# haccess.net
KiCad netlist of a schematic drawn in EAGLE
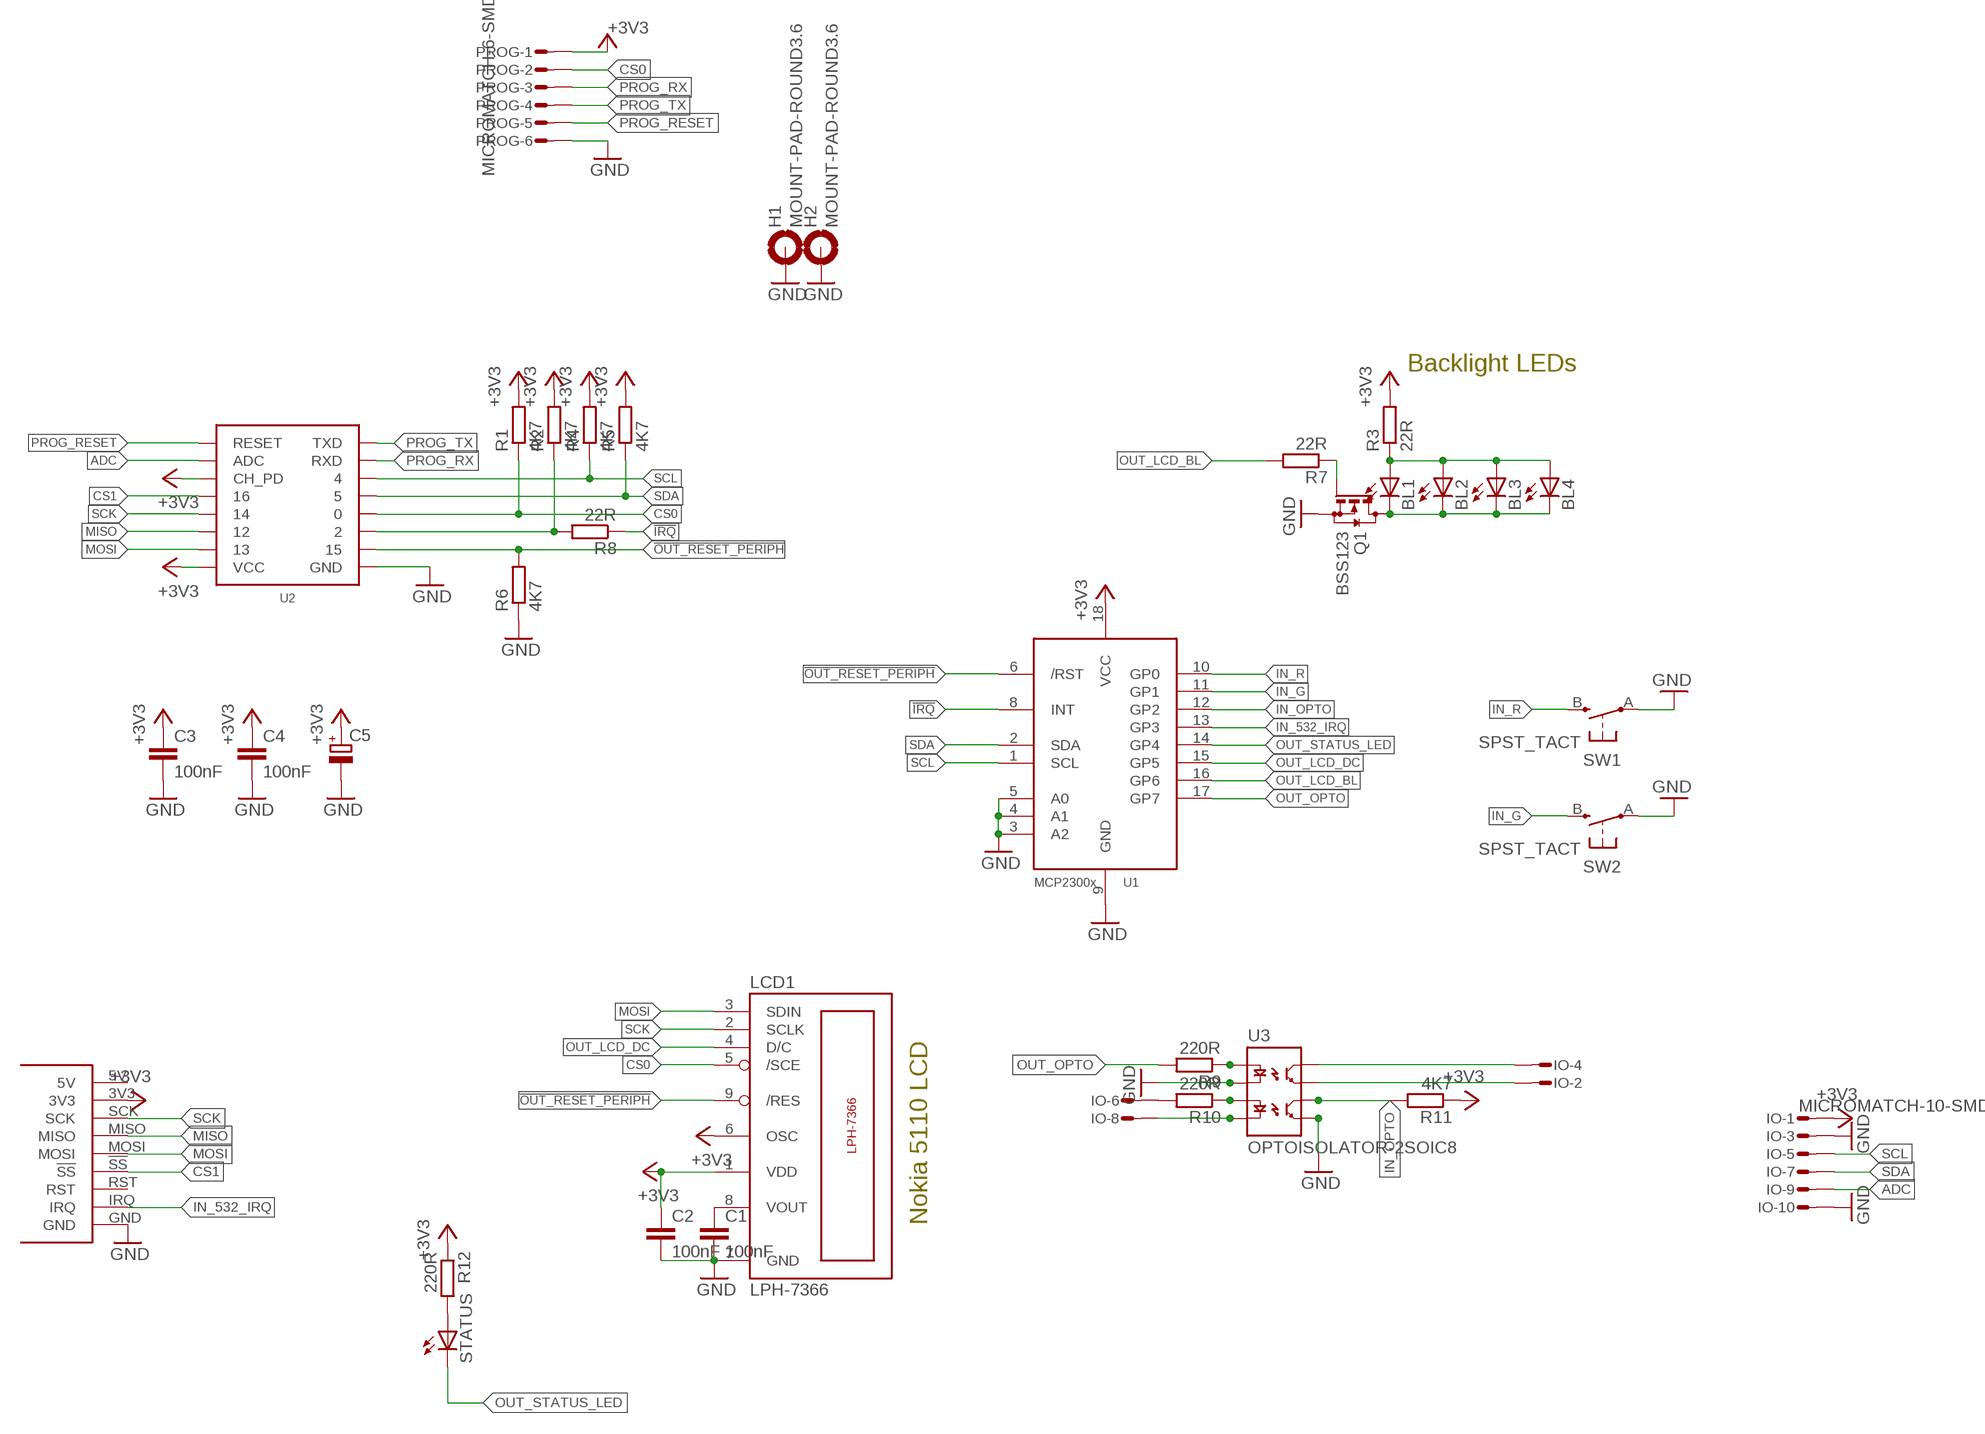
[diagram p0: schematic, sheet 1]

(export (version "E")
  (design (tool "Eeschema 10.0.6"))
  (components
    (comp (ref "BL1")
      (value "LEDCHIPLED_0805")
      (footprint "eagle-import:CHIPLED_0805")
      (libsource (lib "eagle-import") (part "LEDCHIPLED_0805"))
    )
    (comp (ref "BL2")
      (value "LEDCHIPLED_0805")
      (footprint "eagle-import:CHIPLED_0805")
      (libsource (lib "eagle-import") (part "LEDCHIPLED_0805"))
    )
    (comp (ref "BL3")
      (value "LEDCHIPLED_0805")
      (footprint "eagle-import:CHIPLED_0805")
      (libsource (lib "eagle-import") (part "LEDCHIPLED_0805"))
    )
    (comp (ref "BL4")
      (value "LEDCHIPLED_0805")
      (footprint "eagle-import:CHIPLED_0805")
      (libsource (lib "eagle-import") (part "LEDCHIPLED_0805"))
    )
    (comp (ref "C1")
      (value "100nF")
      (footprint "eagle-import:C0805K")
      (libsource (lib "eagle-import") (part "C-EUC0805K"))
    )
    (comp (ref "C2")
      (value "100nF")
      (footprint "eagle-import:C0805K")
      (libsource (lib "eagle-import") (part "C-EUC0805K"))
    )
    (comp (ref "C3")
      (value "100nF")
      (footprint "eagle-import:C0805K")
      (libsource (lib "eagle-import") (part "C-EUC0805K"))
    )
    (comp (ref "C4")
      (value "100nF")
      (footprint "eagle-import:C0805K")
      (libsource (lib "eagle-import") (part "C-EUC0805K"))
    )
    (comp (ref "C5")
      (value "CPOL-EUSMCB")
      (footprint "eagle-import:SMC_B")
      (libsource (lib "eagle-import") (part "CPOL-EUSMCB"))
    )
    (comp (ref "H1")
      (value "MOUNT-PAD-ROUND3.6")
      (footprint "eagle-import:3,6-PAD")
      (libsource (lib "eagle-import") (part "MOUNT-PAD-ROUND3.6"))
    )
    (comp (ref "H2")
      (value "MOUNT-PAD-ROUND3.6")
      (footprint "eagle-import:3,6-PAD")
      (libsource (lib "eagle-import") (part "MOUNT-PAD-ROUND3.6"))
    )
    (comp (ref "IO")
      (value "MICROMATCH-10-SMD")
      (footprint "eagle-import:MICROMATCH-10-SMD")
      (libsource (lib "eagle-import") (part "MICROMATCH-10-SMD"))
    )
    (comp (ref "LCD1")
      (value "LPH-7366")
      (footprint "eagle-import:LPH-7366")
      (libsource (lib "eagle-import") (part "LPH-7366"))
    )
    (comp (ref "PROG")
      (value "MICROMATCH-6-SMD")
      (footprint "eagle-import:MICROMATCH-6-SMD")
      (libsource (lib "eagle-import") (part "MICROMATCH-6-SMD"))
    )
    (comp (ref "Q1")
      (value "BSS123")
      (footprint "eagle-import:SOT23")
      (libsource (lib "eagle-import") (part "BSS123"))
    )
    (comp (ref "R1")
      (value "4K7")
      (footprint "eagle-import:R0603")
      (libsource (lib "eagle-import") (part "R-EU_R0603"))
    )
    (comp (ref "R2")
      (value "4K7")
      (footprint "eagle-import:R0603")
      (libsource (lib "eagle-import") (part "R-EU_R0603"))
    )
    (comp (ref "R3")
      (value "22R")
      (footprint "eagle-import:R0603")
      (libsource (lib "eagle-import") (part "R-EU_R0603"))
    )
    (comp (ref "R4")
      (value "4K7")
      (footprint "eagle-import:R0603")
      (libsource (lib "eagle-import") (part "R-EU_R0603"))
    )
    (comp (ref "R5")
      (value "4K7")
      (footprint "eagle-import:R0603")
      (libsource (lib "eagle-import") (part "R-EU_R0603"))
    )
    (comp (ref "R6")
      (value "4K7")
      (footprint "eagle-import:R0603")
      (libsource (lib "eagle-import") (part "R-EU_R0603"))
    )
    (comp (ref "R7")
      (value "22R")
      (footprint "eagle-import:R0603")
      (libsource (lib "eagle-import") (part "R-EU_R0603"))
    )
    (comp (ref "R8")
      (value "22R")
      (footprint "eagle-import:R0603")
      (libsource (lib "eagle-import") (part "R-EU_R0603"))
    )
    (comp (ref "R9")
      (value "220R")
      (footprint "eagle-import:R0603")
      (libsource (lib "eagle-import") (part "R-EU_R0603"))
    )
    (comp (ref "R10")
      (value "220R")
      (footprint "eagle-import:R0603")
      (libsource (lib "eagle-import") (part "R-EU_R0603"))
    )
    (comp (ref "R11")
      (value "4K7")
      (footprint "eagle-import:R0603")
      (libsource (lib "eagle-import") (part "R-EU_R0603"))
    )
    (comp (ref "R12")
      (value "220R")
      (footprint "eagle-import:R0603")
      (libsource (lib "eagle-import") (part "R-EU_R0603"))
    )
    (comp (ref "STATUS")
      (value "LEDCHIP-LED0805")
      (footprint "eagle-import:CHIP-LED0805")
      (libsource (lib "eagle-import") (part "LEDCHIP-LED0805"))
    )
    (comp (ref "SW1")
      (value "SPST_TACT")
      (footprint "eagle-import:SKPMAPE010")
      (libsource (lib "eagle-import") (part "SPST_TACT"))
    )
    (comp (ref "SW2")
      (value "SPST_TACT")
      (footprint "eagle-import:SKPMAPE010")
      (libsource (lib "eagle-import") (part "SPST_TACT"))
    )
    (comp (ref "U$1")
      (value "PN532SMALLMODULE")
      (footprint "eagle-import:SMALL-MODULE")
      (libsource (lib "eagle-import") (part "PN532SMALLMODULE"))
    )
    (comp (ref "U1")
      (value "MCP2300X/SO")
      (footprint "eagle-import:SO18W")
      (libsource (lib "eagle-import") (part "MCP2300X/SO"))
    )
    (comp (ref "U2")
      (value "ESP826607B")
      (footprint "eagle-import:ESP-07B")
      (libsource (lib "eagle-import") (part "ESP826607B"))
    )
    (comp (ref "U3")
      (value "OPTOISOLATOR-2SOIC8")
      (footprint "eagle-import:SO08-2")
      (libsource (lib "eagle-import") (part "OPTOISOLATOR-2SOIC8"))
    )
  )
  (nets
    (net (code "1") (name "+3V3") (class "Default")
      (node (ref "C2") (pin "1") (pinfunction "1_1") (pintype "passive"))
      (node (ref "C3") (pin "1") (pinfunction "1_1") (pintype "passive"))
      (node (ref "C4") (pin "1") (pinfunction "1_1") (pintype "passive"))
      (node (ref "C5") (pin "+") (pinfunction "+_+") (pintype "passive"))
      (node (ref "IO") (pin "1") (pinfunction "S_1") (pintype "passive"))
      (node (ref "LCD1") (pin "1") (pinfunction "VDD_1") (pintype "power_in"))
      (node (ref "LCD1") (pin "6") (pinfunction "OSC_6") (pintype "passive"))
      (node (ref "PROG") (pin "1") (pinfunction "S_1") (pintype "passive"))
      (node (ref "R1") (pin "2") (pinfunction "2_2") (pintype "passive"))
      (node (ref "R11") (pin "1") (pinfunction "1_1") (pintype "passive"))
      (node (ref "R12") (pin "1") (pinfunction "1_1") (pintype "passive"))
      (node (ref "R2") (pin "2") (pinfunction "2_2") (pintype "passive"))
      (node (ref "R3") (pin "2") (pinfunction "2_2") (pintype "passive"))
      (node (ref "R4") (pin "2") (pinfunction "2_2") (pintype "passive"))
      (node (ref "R5") (pin "2") (pinfunction "2_2") (pintype "passive"))
      (node (ref "U$1") (pin "3V3") (pinfunction "3V3_3V3") (pintype "bidirectional"))
      (node (ref "U1") (pin "18") (pinfunction "VCC_18") (pintype "power_in"))
      (node (ref "U2") (pin "CH_PD") (pinfunction "CH_PD_CH_PD") (pintype "input"))
      (node (ref "U2") (pin "VCC") (pinfunction "VCC_VCC") (pintype "power_in"))
    )
    (net (code "2") (name "/~{IRQ}") (class "Default")
      (node (ref "R8") (pin "1") (pinfunction "1_1") (pintype "passive"))
      (node (ref "U1") (pin "8") (pinfunction "INT_8") (pintype "output"))
    )
    (net (code "3") (name "/~{OUT_RESET_PERIPH}") (class "Default")
      (node (ref "LCD1") (pin "9") (pinfunction "/RES_9") (pintype "input"))
      (node (ref "R6") (pin "2") (pinfunction "2_2") (pintype "passive"))
      (node (ref "U1") (pin "6") (pinfunction "/RST_6") (pintype "input"))
      (node (ref "U2") (pin "GPIO15") (pinfunction "15_GPIO15") (pintype "bidirectional"))
    )
    (net (code "4") (name "ADC") (class "Default")
      (node (ref "IO") (pin "9") (pinfunction "S_9") (pintype "passive"))
      (node (ref "U2") (pin "ADC") (pinfunction "ADC_ADC") (pintype "input"))
    )
    (net (code "5") (name "CS0") (class "Default")
      (node (ref "LCD1") (pin "5") (pinfunction "/SCE_5") (pintype "input"))
      (node (ref "PROG") (pin "2") (pinfunction "S_2") (pintype "passive"))
      (node (ref "R1") (pin "1") (pinfunction "1_1") (pintype "passive"))
      (node (ref "U2") (pin "GPIO0") (pinfunction "0_GPIO0") (pintype "bidirectional"))
    )
    (net (code "6") (name "CS1") (class "Default")
      (node (ref "U$1") (pin "!SS") (pinfunction "~{SS}_!SS") (pintype "bidirectional"))
      (node (ref "U2") (pin "GPIO16") (pinfunction "16_GPIO16") (pintype "bidirectional"))
    )
    (net (code "7") (name "GND") (class "Default")
      (node (ref "C1") (pin "2") (pinfunction "2_2") (pintype "passive"))
      (node (ref "C2") (pin "2") (pinfunction "2_2") (pintype "passive"))
      (node (ref "C3") (pin "2") (pinfunction "2_2") (pintype "passive"))
      (node (ref "C4") (pin "2") (pinfunction "2_2") (pintype "passive"))
      (node (ref "C5") (pin "-") (pinfunction "-_-") (pintype "passive"))
      (node (ref "H1") (pin "B3,6") (pinfunction "MOUNT_B3,6") (pintype "passive"))
      (node (ref "H2") (pin "B3,6") (pinfunction "MOUNT_B3,6") (pintype "passive"))
      (node (ref "IO") (pin "10") (pinfunction "S_10") (pintype "passive"))
      (node (ref "IO") (pin "3") (pinfunction "S_3") (pintype "passive"))
      (node (ref "LCD1") (pin "7") (pinfunction "GND_7") (pintype "power_in"))
      (node (ref "PROG") (pin "6") (pinfunction "S_6") (pintype "passive"))
      (node (ref "Q1") (pin "2") (pinfunction "S_2") (pintype "passive"))
      (node (ref "R6") (pin "1") (pinfunction "1_1") (pintype "passive"))
      (node (ref "SW1") (pin "A") (pinfunction "P_A") (pintype "passive"))
      (node (ref "SW2") (pin "A") (pinfunction "P_A") (pintype "passive"))
      (node (ref "U$1") (pin "GND") (pinfunction "GND_GND") (pintype "bidirectional"))
      (node (ref "U1") (pin "3") (pinfunction "A2_3") (pintype "input"))
      (node (ref "U1") (pin "4") (pinfunction "A1_4") (pintype "input"))
      (node (ref "U1") (pin "5") (pinfunction "A0_5") (pintype "input"))
      (node (ref "U1") (pin "9") (pinfunction "GND_9") (pintype "power_in"))
      (node (ref "U2") (pin "GND") (pinfunction "GND_GND") (pintype "power_in"))
      (node (ref "U3") (pin "2") (pinfunction "C1_2") (pintype "bidirectional"))
      (node (ref "U3") (pin "5") (pinfunction "EM2_5") (pintype "bidirectional"))
    )
    (net (code "8") (name "IN_532_IRQ") (class "Default")
      (node (ref "U$1") (pin "IRQ") (pinfunction "IRQ_IRQ") (pintype "bidirectional"))
      (node (ref "U1") (pin "13") (pinfunction "GP3_13") (pintype "bidirectional"))
    )
    (net (code "9") (name "IN_G") (class "Default")
      (node (ref "SW2") (pin "B") (pinfunction "S_B") (pintype "passive"))
      (node (ref "U1") (pin "11") (pinfunction "GP1_11") (pintype "bidirectional"))
    )
    (net (code "10") (name "IN_OPTO") (class "Default")
      (node (ref "R11") (pin "2") (pinfunction "2_2") (pintype "passive"))
      (node (ref "U1") (pin "12") (pinfunction "GP2_12") (pintype "bidirectional"))
      (node (ref "U3") (pin "6") (pinfunction "CL2_6") (pintype "bidirectional"))
    )
    (net (code "11") (name "IN_R") (class "Default")
      (node (ref "SW1") (pin "B") (pinfunction "S_B") (pintype "passive"))
      (node (ref "U1") (pin "10") (pinfunction "GP0_10") (pintype "bidirectional"))
    )
    (net (code "12") (name "MISO") (class "Default")
      (node (ref "U$1") (pin "MISO") (pinfunction "MISO_MISO") (pintype "bidirectional"))
      (node (ref "U2") (pin "GPIO12") (pinfunction "12_GPIO12") (pintype "bidirectional"))
    )
    (net (code "13") (name "MOSI") (class "Default")
      (node (ref "LCD1") (pin "3") (pinfunction "SDIN_3") (pintype "input"))
      (node (ref "U$1") (pin "MOSI") (pinfunction "MOSI_MOSI") (pintype "bidirectional"))
      (node (ref "U2") (pin "GPIO13") (pinfunction "13_GPIO13") (pintype "bidirectional"))
    )
    (net (code "14") (name "Net-(BL1-PadA)") (class "Default")
      (node (ref "BL1") (pin "A") (pinfunction "A_A") (pintype "passive"))
      (node (ref "BL2") (pin "A") (pinfunction "A_A") (pintype "passive"))
      (node (ref "BL3") (pin "A") (pinfunction "A_A") (pintype "passive"))
      (node (ref "BL4") (pin "A") (pinfunction "A_A") (pintype "passive"))
      (node (ref "R3") (pin "1") (pinfunction "1_1") (pintype "passive"))
    )
    (net (code "15") (name "Net-(IOC-S)") (class "Default")
      (node (ref "IO") (pin "2") (pinfunction "S_2") (pintype "passive"))
      (node (ref "U3") (pin "7") (pinfunction "EM1_7") (pintype "bidirectional"))
    )
    (net (code "16") (name "Net-(IOE-S)") (class "Default")
      (node (ref "IO") (pin "4") (pinfunction "S_4") (pintype "passive"))
      (node (ref "U3") (pin "8") (pinfunction "CL1_8") (pintype "bidirectional"))
    )
    (net (code "17") (name "Net-(IOG-S)") (class "Default")
      (node (ref "IO") (pin "6") (pinfunction "S_6") (pintype "passive"))
      (node (ref "R10") (pin "2") (pinfunction "2_2") (pintype "passive"))
    )
    (net (code "18") (name "Net-(IOI-S)") (class "Default")
      (node (ref "IO") (pin "8") (pinfunction "S_8") (pintype "passive"))
      (node (ref "U3") (pin "4") (pinfunction "C2_4") (pintype "bidirectional"))
    )
    (net (code "19") (name "Net-(LCD1-VOUT)") (class "Default")
      (node (ref "C1") (pin "1") (pinfunction "1_1") (pintype "passive"))
      (node (ref "LCD1") (pin "8") (pinfunction "VOUT_8") (pintype "passive"))
    )
    (net (code "20") (name "Net-(Q1-D)") (class "Default")
      (node (ref "BL1") (pin "C") (pinfunction "C_C") (pintype "passive"))
      (node (ref "BL2") (pin "C") (pinfunction "C_C") (pintype "passive"))
      (node (ref "BL3") (pin "C") (pinfunction "C_C") (pintype "passive"))
      (node (ref "BL4") (pin "C") (pinfunction "C_C") (pintype "passive"))
      (node (ref "Q1") (pin "3") (pinfunction "D_3") (pintype "passive"))
    )
    (net (code "21") (name "Net-(Q1-G)") (class "Default")
      (node (ref "Q1") (pin "1") (pinfunction "G_1") (pintype "passive"))
      (node (ref "R7") (pin "1") (pinfunction "1_1") (pintype "passive"))
    )
    (net (code "22") (name "Net-(R12-Pad2)") (class "Default")
      (node (ref "R12") (pin "2") (pinfunction "2_2") (pintype "passive"))
      (node (ref "STATUS") (pin "A") (pinfunction "A_A") (pintype "passive"))
    )
    (net (code "23") (name "Net-(U2-2)") (class "Default")
      (node (ref "R2") (pin "1") (pinfunction "1_1") (pintype "passive"))
      (node (ref "R8") (pin "2") (pinfunction "2_2") (pintype "passive"))
      (node (ref "U2") (pin "GPIO2") (pinfunction "2_GPIO2") (pintype "bidirectional"))
    )
    (net (code "24") (name "Net-(U3-A1)") (class "Default")
      (node (ref "R9") (pin "1") (pinfunction "1_1") (pintype "passive"))
      (node (ref "U3") (pin "1") (pinfunction "A1_1") (pintype "bidirectional"))
    )
    (net (code "25") (name "Net-(U3-A2)") (class "Default")
      (node (ref "R10") (pin "1") (pinfunction "1_1") (pintype "passive"))
      (node (ref "U3") (pin "3") (pinfunction "A2_3") (pintype "bidirectional"))
    )
    (net (code "26") (name "OUT_LCD_BL") (class "Default")
      (node (ref "R7") (pin "2") (pinfunction "2_2") (pintype "passive"))
      (node (ref "U1") (pin "16") (pinfunction "GP6_16") (pintype "bidirectional"))
    )
    (net (code "27") (name "OUT_LCD_DC") (class "Default")
      (node (ref "LCD1") (pin "4") (pinfunction "D/C_4") (pintype "input"))
      (node (ref "U1") (pin "15") (pinfunction "GP5_15") (pintype "bidirectional"))
    )
    (net (code "28") (name "OUT_OPTO") (class "Default")
      (node (ref "R9") (pin "2") (pinfunction "2_2") (pintype "passive"))
      (node (ref "U1") (pin "17") (pinfunction "GP7_17") (pintype "bidirectional"))
    )
    (net (code "29") (name "OUT_STATUS_LED") (class "Default")
      (node (ref "STATUS") (pin "C") (pinfunction "C_C") (pintype "passive"))
      (node (ref "U1") (pin "14") (pinfunction "GP4_14") (pintype "bidirectional"))
    )
    (net (code "30") (name "PROG_RESET") (class "Default")
      (node (ref "PROG") (pin "5") (pinfunction "S_5") (pintype "passive"))
      (node (ref "U2") (pin "RESET") (pinfunction "RESET_RESET") (pintype "input"))
    )
    (net (code "31") (name "PROG_RX") (class "Default")
      (node (ref "PROG") (pin "3") (pinfunction "S_3") (pintype "passive"))
      (node (ref "U2") (pin "RXD") (pinfunction "RXD_RXD") (pintype "input"))
    )
    (net (code "32") (name "PROG_TX") (class "Default")
      (node (ref "PROG") (pin "4") (pinfunction "S_4") (pintype "passive"))
      (node (ref "U2") (pin "TXD") (pinfunction "TXD_TXD") (pintype "output"))
    )
    (net (code "33") (name "SCK") (class "Default")
      (node (ref "LCD1") (pin "2") (pinfunction "SCLK_2") (pintype "input"))
      (node (ref "U$1") (pin "SCK") (pinfunction "SCK_SCK") (pintype "bidirectional"))
      (node (ref "U2") (pin "GPIO14") (pinfunction "14_GPIO14") (pintype "bidirectional"))
    )
    (net (code "34") (name "SCL") (class "Default")
      (node (ref "IO") (pin "5") (pinfunction "S_5") (pintype "passive"))
      (node (ref "R4") (pin "1") (pinfunction "1_1") (pintype "passive"))
      (node (ref "U1") (pin "1") (pinfunction "SCL_1") (pintype "bidirectional"))
      (node (ref "U2") (pin "GPIO4") (pinfunction "4_GPIO4") (pintype "bidirectional"))
    )
    (net (code "35") (name "SDA") (class "Default")
      (node (ref "IO") (pin "7") (pinfunction "S_7") (pintype "passive"))
      (node (ref "R5") (pin "1") (pinfunction "1_1") (pintype "passive"))
      (node (ref "U1") (pin "2") (pinfunction "SDA_2") (pintype "bidirectional"))
      (node (ref "U2") (pin "GPIO5") (pinfunction "5_GPIO5") (pintype "bidirectional"))
    )
    (net (code "36") (name "unconnected-(U$1-Pad5V)") (class "Default")
      (node (ref "U$1") (pin "5V") (pinfunction "5V_5V") (pintype "bidirectional"))
    )
    (net (code "37") (name "unconnected-(U$1-PadRST)") (class "Default")
      (node (ref "U$1") (pin "RST") (pinfunction "RST_RST") (pintype "bidirectional"))
    )
  )
)
